# Gamepad_Sensors.net
KiCad netlist of a schematic drawn in Altium Designer
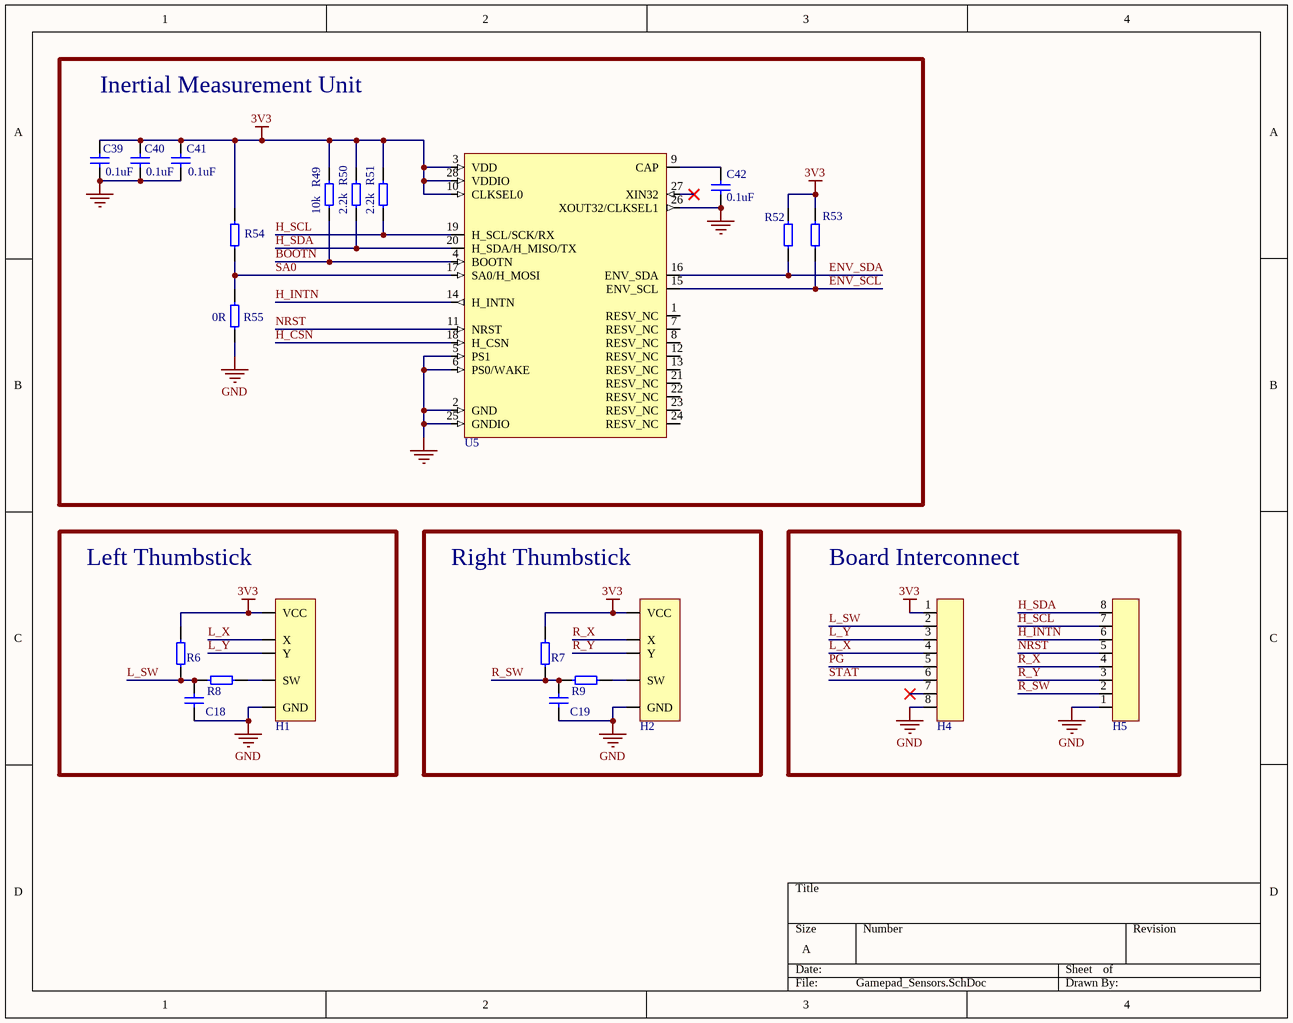
[diagram p0: Gamepad_Sensors.SchDoc]

(export (version "E")
  (design (tool "Eeschema 10.0.6"))
  (components
    (comp (ref "C18")
      (value "Capacitor")
      (footprint "0603 Capacitor")
      (libsource (lib "MoldsvorLibrary") (part "Capacitor"))
    )
    (comp (ref "C19")
      (value "Capacitor")
      (footprint "0603 Capacitor")
      (libsource (lib "MoldsvorLibrary") (part "Capacitor"))
    )
    (comp (ref "C39")
      (value "0.1uF")
      (footprint "0603 Capacitor")
      (libsource (lib "MoldsvorPassives") (part "Capacitor"))
    )
    (comp (ref "C40")
      (value "0.1uF")
      (footprint "0603 Capacitor")
      (libsource (lib "MoldsvorPassives") (part "Capacitor"))
    )
    (comp (ref "C41")
      (value "0.1uF")
      (footprint "0603 Capacitor")
      (libsource (lib "MoldsvorPassives") (part "Capacitor"))
    )
    (comp (ref "C42")
      (value "0.1uF")
      (footprint "0603 Capacitor")
      (libsource (lib "MoldsvorPassives") (part "Capacitor"))
    )
    (comp (ref "H1")
      (value "Left Thumbstick")
      (footprint "THB001P")
      (libsource (lib "Gamepad_Schematic_Library") (part "Thumbstick"))
    )
    (comp (ref "H2")
      (value "Right Thumbstick")
      (footprint "THB001P")
      (libsource (lib "Gamepad_Schematic_Library") (part "Thumbstick"))
    )
    (comp (ref "H4")
      (value "8x1 Header")
      (footprint "SMD Header Female")
      (libsource (lib "") (part "8x1 Header_1"))
    )
    (comp (ref "H5")
      (value "8x1 Header")
      (footprint "SMD Header Female")
      (libsource (lib "Gamepad_Schematic_Library") (part "8x1 Header"))
    )
    (comp (ref "R6")
      (value "Resistor")
      (footprint "0603 Resistor")
      (libsource (lib "MoldsvorLibrary") (part "Resistor"))
    )
    (comp (ref "R7")
      (value "Resistor")
      (footprint "0603 Resistor")
      (libsource (lib "MoldsvorLibrary") (part "Resistor"))
    )
    (comp (ref "R8")
      (value "Resistor")
      (footprint "0603 Resistor")
      (libsource (lib "MoldsvorLibrary") (part "Resistor"))
    )
    (comp (ref "R9")
      (value "Resistor")
      (footprint "0603 Resistor")
      (libsource (lib "MoldsvorLibrary") (part "Resistor"))
    )
    (comp (ref "R49")
      (value "10k")
      (footprint "0603 Resistor")
      (libsource (lib "MoldsvorLibrary") (part "Resistor"))
    )
    (comp (ref "R50")
      (value "2.2k")
      (footprint "0603 Resistor")
      (libsource (lib "MoldsvorPassives") (part "Resistor"))
    )
    (comp (ref "R51")
      (value "2.2k")
      (footprint "0603 Resistor")
      (libsource (lib "MoldsvorPassives") (part "Resistor"))
    )
    (comp (ref "R52")
      (value "Resistor")
      (footprint "0603 Resistor")
      (libsource (lib "MoldsvorPassives") (part "Resistor"))
    )
    (comp (ref "R53")
      (value "Resistor")
      (footprint "0603 Resistor")
      (libsource (lib "MoldsvorPassives") (part "Resistor"))
    )
    (comp (ref "R54")
      (value "Resistor")
      (footprint "0603 Resistor")
      (libsource (lib "MoldsvorLibrary") (part "Resistor"))
    )
    (comp (ref "R55")
      (value "0R")
      (footprint "0603 Resistor")
      (libsource (lib "MoldsvorLibrary") (part "Resistor"))
    )
    (comp (ref "U5")
      (value "BNO080")
      (footprint "BNO080")
      (description "IMU ACCEL/GYRO/MAG I2C 32BIT")
      (libsource (lib "Gamepad_Schematic_Library") (part "BNO080"))
    )
  )
  (nets
    (net (code "1") (name "/BOOTN") (class "Default")
      (node (ref "R49") (pin "1") (pintype "passive"))
      (node (ref "U5") (pin "4") (pinfunction "BOOTN_4") (pintype "input"))
    )
    (net (code "2") (name "/ENV_SCL") (class "Default")
      (node (ref "R53") (pin "1") (pintype "passive"))
      (node (ref "U5") (pin "15") (pinfunction "ENV_SCL_15") (pintype "bidirectional"))
    )
    (net (code "3") (name "/ENV_SDA") (class "Default")
      (node (ref "R52") (pin "1") (pintype "passive"))
      (node (ref "U5") (pin "16") (pinfunction "ENV_SDA_16") (pintype "bidirectional"))
    )
    (net (code "4") (name "/H_CSN") (class "Default")
      (node (ref "U5") (pin "18") (pinfunction "H_CSN_18") (pintype "input"))
    )
    (net (code "5") (name "/H_INTN") (class "Default")
      (node (ref "H5") (pin "6") (pinfunction "6_6") (pintype "passive"))
      (node (ref "U5") (pin "14") (pinfunction "H_INTN_14") (pintype "output"))
    )
    (net (code "6") (name "/H_SCL") (class "Default")
      (node (ref "H5") (pin "7") (pinfunction "7_7") (pintype "passive"))
      (node (ref "R51") (pin "1") (pintype "passive"))
      (node (ref "U5") (pin "19") (pinfunction "H_SCL/SCK/RX_19") (pintype "bidirectional"))
    )
    (net (code "7") (name "/H_SDA") (class "Default")
      (node (ref "H5") (pin "8") (pinfunction "8_8") (pintype "passive"))
      (node (ref "R50") (pin "1") (pintype "passive"))
      (node (ref "U5") (pin "20") (pinfunction "H_SDA/H_MISO/TX_20") (pintype "bidirectional"))
    )
    (net (code "8") (name "/L_SW") (class "Default")
      (node (ref "C18") (pin "2") (pinfunction "2_2") (pintype "passive"))
      (node (ref "H4") (pin "2") (pinfunction "2_2") (pintype "passive"))
      (node (ref "R6") (pin "1") (pintype "passive"))
      (node (ref "R8") (pin "1") (pintype "passive"))
    )
    (net (code "9") (name "/L_X") (class "Default")
      (node (ref "H1") (pin "2") (pinfunction "X_2") (pintype "passive"))
      (node (ref "H4") (pin "4") (pinfunction "4_4") (pintype "passive"))
    )
    (net (code "10") (name "/L_Y") (class "Default")
      (node (ref "H1") (pin "3") (pinfunction "Y_3") (pintype "passive"))
      (node (ref "H4") (pin "3") (pinfunction "3_3") (pintype "passive"))
    )
    (net (code "11") (name "/NRST") (class "Default")
      (node (ref "H5") (pin "5") (pinfunction "5_5") (pintype "passive"))
      (node (ref "U5") (pin "11") (pinfunction "NRST_11") (pintype "input"))
    )
    (net (code "12") (name "/PG") (class "Default")
      (node (ref "H4") (pin "5") (pinfunction "5_5") (pintype "passive"))
    )
    (net (code "13") (name "/R_SW") (class "Default")
      (node (ref "C19") (pin "2") (pinfunction "2_2") (pintype "passive"))
      (node (ref "H5") (pin "2") (pinfunction "2_2") (pintype "passive"))
      (node (ref "R7") (pin "1") (pintype "passive"))
      (node (ref "R9") (pin "1") (pintype "passive"))
    )
    (net (code "14") (name "/R_X") (class "Default")
      (node (ref "H2") (pin "2") (pinfunction "X_2") (pintype "passive"))
      (node (ref "H5") (pin "4") (pinfunction "4_4") (pintype "passive"))
    )
    (net (code "15") (name "/R_Y") (class "Default")
      (node (ref "H2") (pin "3") (pinfunction "Y_3") (pintype "passive"))
      (node (ref "H5") (pin "3") (pinfunction "3_3") (pintype "passive"))
    )
    (net (code "16") (name "/SA0") (class "Default")
      (node (ref "R54") (pin "1") (pintype "passive"))
      (node (ref "R55") (pin "2") (pintype "passive"))
      (node (ref "U5") (pin "17") (pinfunction "SA0/H_MOSI_17") (pintype "input"))
    )
    (net (code "17") (name "/STAT") (class "Default")
      (node (ref "H4") (pin "6") (pinfunction "6_6") (pintype "passive"))
    )
    (net (code "18") (name "3V3") (class "Default")
      (node (ref "C39") (pin "2") (pinfunction "2_2") (pintype "passive"))
      (node (ref "C40") (pin "1") (pinfunction "1_1") (pintype "passive"))
      (node (ref "C41") (pin "2") (pinfunction "2_2") (pintype "passive"))
      (node (ref "H1") (pin "1") (pinfunction "VCC_1") (pintype "passive"))
      (node (ref "H2") (pin "1") (pinfunction "VCC_1") (pintype "passive"))
      (node (ref "H4") (pin "1") (pinfunction "1_1") (pintype "passive"))
      (node (ref "R49") (pin "2") (pintype "passive"))
      (node (ref "R50") (pin "2") (pintype "passive"))
      (node (ref "R51") (pin "2") (pintype "passive"))
      (node (ref "R52") (pin "2") (pintype "passive"))
      (node (ref "R53") (pin "2") (pintype "passive"))
      (node (ref "R54") (pin "2") (pintype "passive"))
      (node (ref "R6") (pin "2") (pintype "passive"))
      (node (ref "R7") (pin "2") (pintype "passive"))
      (node (ref "U5") (pin "10") (pinfunction "CLKSEL0_10") (pintype "input"))
      (node (ref "U5") (pin "28") (pinfunction "VDDIO_28") (pintype "input"))
      (node (ref "U5") (pin "3") (pinfunction "VDD_3") (pintype "input"))
    )
    (net (code "19") (name "GND") (class "Default")
      (node (ref "C18") (pin "1") (pinfunction "1_1") (pintype "passive"))
      (node (ref "C19") (pin "1") (pinfunction "1_1") (pintype "passive"))
      (node (ref "C39") (pin "1") (pinfunction "1_1") (pintype "passive"))
      (node (ref "C40") (pin "2") (pinfunction "2_2") (pintype "passive"))
      (node (ref "C41") (pin "1") (pinfunction "1_1") (pintype "passive"))
      (node (ref "C42") (pin "1") (pinfunction "1_1") (pintype "passive"))
      (node (ref "H1") (pin "5") (pinfunction "GND_5") (pintype "passive"))
      (node (ref "H2") (pin "5") (pinfunction "GND_5") (pintype "passive"))
      (node (ref "H4") (pin "8") (pinfunction "8_8") (pintype "passive"))
      (node (ref "H5") (pin "1") (pinfunction "1_1") (pintype "passive"))
      (node (ref "R55") (pin "1") (pintype "passive"))
      (node (ref "U5") (pin "2") (pinfunction "GND_2") (pintype "input"))
      (node (ref "U5") (pin "25") (pinfunction "GNDIO_25") (pintype "input"))
      (node (ref "U5") (pin "26") (pinfunction "XOUT32/CLKSEL1_26") (pintype "output"))
      (node (ref "U5") (pin "5") (pinfunction "PS1_5") (pintype "input"))
      (node (ref "U5") (pin "6") (pinfunction "PS0/WAKE_6") (pintype "input"))
    )
    (net (code "20") (name "Net-(H1-SW)") (class "Default")
      (node (ref "H1") (pin "4") (pinfunction "SW_4") (pintype "passive"))
      (node (ref "R8") (pin "2") (pintype "passive"))
    )
    (net (code "21") (name "Net-(H2-SW)") (class "Default")
      (node (ref "H2") (pin "4") (pinfunction "SW_4") (pintype "passive"))
      (node (ref "R9") (pin "2") (pintype "passive"))
    )
    (net (code "22") (name "Net-(U5-CAP)") (class "Default")
      (node (ref "C42") (pin "2") (pinfunction "2_2") (pintype "passive"))
      (node (ref "U5") (pin "9") (pinfunction "CAP_9") (pintype "passive"))
    )
    (net (code "23") (name "unconnected-(H4-Pad7)") (class "Default")
      (node (ref "H4") (pin "7") (pinfunction "7_7") (pintype "passive+no_connect"))
    )
    (net (code "24") (name "unconnected-(U5-RESV_NC-Pad1)") (class "Default")
      (node (ref "U5") (pin "1") (pinfunction "RESV_NC_1") (pintype "passive"))
    )
    (net (code "25") (name "unconnected-(U5-RESV_NC-Pad7)") (class "Default")
      (node (ref "U5") (pin "7") (pinfunction "RESV_NC_7") (pintype "passive"))
    )
    (net (code "26") (name "unconnected-(U5-RESV_NC-Pad8)") (class "Default")
      (node (ref "U5") (pin "8") (pinfunction "RESV_NC_8") (pintype "passive"))
    )
    (net (code "27") (name "unconnected-(U5-RESV_NC-Pad12)") (class "Default")
      (node (ref "U5") (pin "12") (pinfunction "RESV_NC_12") (pintype "passive"))
    )
    (net (code "28") (name "unconnected-(U5-RESV_NC-Pad13)") (class "Default")
      (node (ref "U5") (pin "13") (pinfunction "RESV_NC_13") (pintype "passive"))
    )
    (net (code "29") (name "unconnected-(U5-RESV_NC-Pad21)") (class "Default")
      (node (ref "U5") (pin "21") (pinfunction "RESV_NC_21") (pintype "passive"))
    )
    (net (code "30") (name "unconnected-(U5-RESV_NC-Pad22)") (class "Default")
      (node (ref "U5") (pin "22") (pinfunction "RESV_NC_22") (pintype "passive"))
    )
    (net (code "31") (name "unconnected-(U5-RESV_NC-Pad23)") (class "Default")
      (node (ref "U5") (pin "23") (pinfunction "RESV_NC_23") (pintype "passive"))
    )
    (net (code "32") (name "unconnected-(U5-RESV_NC-Pad24)") (class "Default")
      (node (ref "U5") (pin "24") (pinfunction "RESV_NC_24") (pintype "passive"))
    )
    (net (code "33") (name "unconnected-(U5-XIN32-Pad27)") (class "Default")
      (node (ref "U5") (pin "27") (pinfunction "XIN32_27") (pintype "input+no_connect"))
    )
  )
)
